# 8_SD.net
KiCad netlist of a schematic drawn in Altium Designer
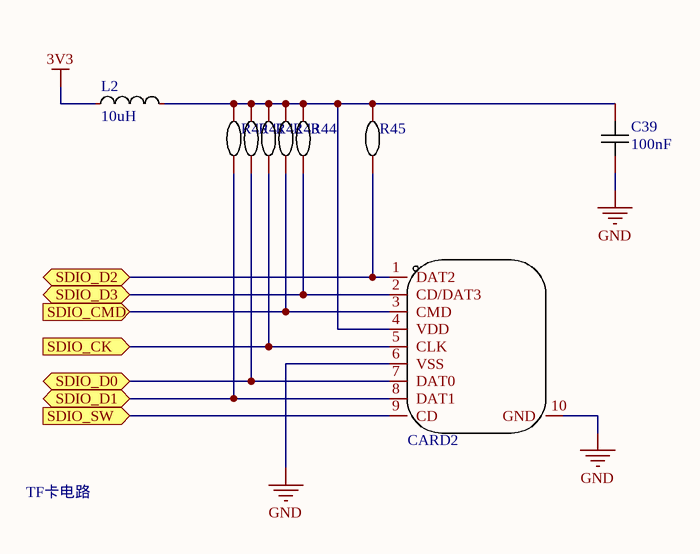
[diagram p0: 8_SD卡电路.SchDoc]

(export (version "E")
  (design (tool "Eeschema 10.0.6"))
  (components
    (comp (ref "C39")
      (value "100nF")
      (footprint "0603C")
      (fields (field (name "NAME") "100nF"))
      (libsource (lib "5_CPU_TF卡.schdoc") (part "CAP_0603"))
    )
    (comp (ref "CARD2")
      (value "TF-02A")
      (footprint "TF-SMD_TF-02")
      (libsource (lib "5_CPU_TF卡.schdoc") (part "TF-02A"))
    )
    (comp (ref "L2")
      (value "10uH")
      (footprint "L0603")
      (fields (field (name "NAME") "10uH"))
      (libsource (lib "5_CPU_TF卡.schdoc") (part "L_0603"))
    )
    (comp (ref "R40")
      (value "~")
      (footprint "0402R")
      (fields (field (name "MANUFACTURER PART") "RC0402FR-0710KL"))
      (libsource (lib "5_CPU_TF卡.schdoc") (part "RC0402FR-0710KL"))
    )
    (comp (ref "R41")
      (value "~")
      (footprint "0402R")
      (fields (field (name "MANUFACTURER PART") "RC0402FR-0710KL"))
      (libsource (lib "5_CPU_TF卡.schdoc") (part "RC0402FR-0710KL"))
    )
    (comp (ref "R42")
      (value "~")
      (footprint "0402R")
      (fields (field (name "MANUFACTURER PART") "RC0402FR-0710KL"))
      (libsource (lib "5_CPU_TF卡.schdoc") (part "RC0402FR-0710KL"))
    )
    (comp (ref "R43")
      (value "~")
      (footprint "0402R")
      (fields (field (name "MANUFACTURER PART") "RC0402FR-0710KL"))
      (libsource (lib "5_CPU_TF卡.schdoc") (part "RC0402FR-0710KL"))
    )
    (comp (ref "R44")
      (value "~")
      (footprint "0402R")
      (fields (field (name "MANUFACTURER PART") "RC0402FR-0710KL"))
      (libsource (lib "5_CPU_TF卡.schdoc") (part "RC0402FR-0710KL"))
    )
    (comp (ref "R45")
      (value "~")
      (footprint "0402R")
      (fields (field (name "MANUFACTURER PART") "RC0402FR-0710KL"))
      (libsource (lib "5_CPU_TF卡.schdoc") (part "RC0402FR-0710KL"))
    )
  )
  (nets
    (net (code "1") (name "/SDIO_CK") (class "Default")
      (node (ref "CARD2") (pin "5") (pinfunction "CLK_5") (pintype "passive"))
      (node (ref "R42") (pin "1") (pinfunction "1_1") (pintype "passive"))
    )
    (net (code "2") (name "/SDIO_CMD") (class "Default")
      (node (ref "CARD2") (pin "3") (pinfunction "CMD_3") (pintype "passive"))
      (node (ref "R43") (pin "1") (pinfunction "1_1") (pintype "passive"))
    )
    (net (code "3") (name "/SDIO_D0") (class "Default")
      (node (ref "CARD2") (pin "7") (pinfunction "DAT0_7") (pintype "passive"))
      (node (ref "R41") (pin "1") (pinfunction "1_1") (pintype "passive"))
    )
    (net (code "4") (name "/SDIO_D1") (class "Default")
      (node (ref "CARD2") (pin "8") (pinfunction "DAT1_8") (pintype "passive"))
      (node (ref "R40") (pin "1") (pinfunction "1_1") (pintype "passive"))
    )
    (net (code "5") (name "/SDIO_D2") (class "Default")
      (node (ref "CARD2") (pin "1") (pinfunction "DAT2_1") (pintype "passive"))
      (node (ref "R45") (pin "1") (pinfunction "1_1") (pintype "passive"))
    )
    (net (code "6") (name "/SDIO_D3") (class "Default")
      (node (ref "CARD2") (pin "2") (pinfunction "CD/DAT3_2") (pintype "passive"))
      (node (ref "R44") (pin "1") (pinfunction "1_1") (pintype "passive"))
    )
    (net (code "7") (name "/SDIO_SW") (class "Default")
      (node (ref "CARD2") (pin "9") (pinfunction "CD_9") (pintype "passive"))
    )
    (net (code "8") (name "3V3") (class "Default")
      (node (ref "L2") (pin "1") (pinfunction "1_1") (pintype "passive"))
    )
    (net (code "9") (name "GND") (class "Default")
      (node (ref "C39") (pin "1") (pinfunction "1_1") (pintype "passive"))
      (node (ref "CARD2") (pin "10") (pinfunction "GND_10") (pintype "passive"))
      (node (ref "CARD2") (pin "6") (pinfunction "VSS_6") (pintype "passive"))
    )
    (net (code "10") (name "Net-(CARD2-VDD)") (class "Default")
      (node (ref "C39") (pin "2") (pinfunction "2_2") (pintype "passive"))
      (node (ref "CARD2") (pin "4") (pinfunction "VDD_4") (pintype "passive"))
      (node (ref "L2") (pin "2") (pinfunction "2_2") (pintype "passive"))
      (node (ref "R40") (pin "2") (pinfunction "2_2") (pintype "passive"))
      (node (ref "R41") (pin "2") (pinfunction "2_2") (pintype "passive"))
      (node (ref "R42") (pin "2") (pinfunction "2_2") (pintype "passive"))
      (node (ref "R43") (pin "2") (pinfunction "2_2") (pintype "passive"))
      (node (ref "R44") (pin "2") (pinfunction "2_2") (pintype "passive"))
      (node (ref "R45") (pin "2") (pinfunction "2_2") (pintype "passive"))
    )
  )
)
